# SCH_Business-Card_2024-07-06.net
KiCad netlist of a schematic drawn in EasyEDA
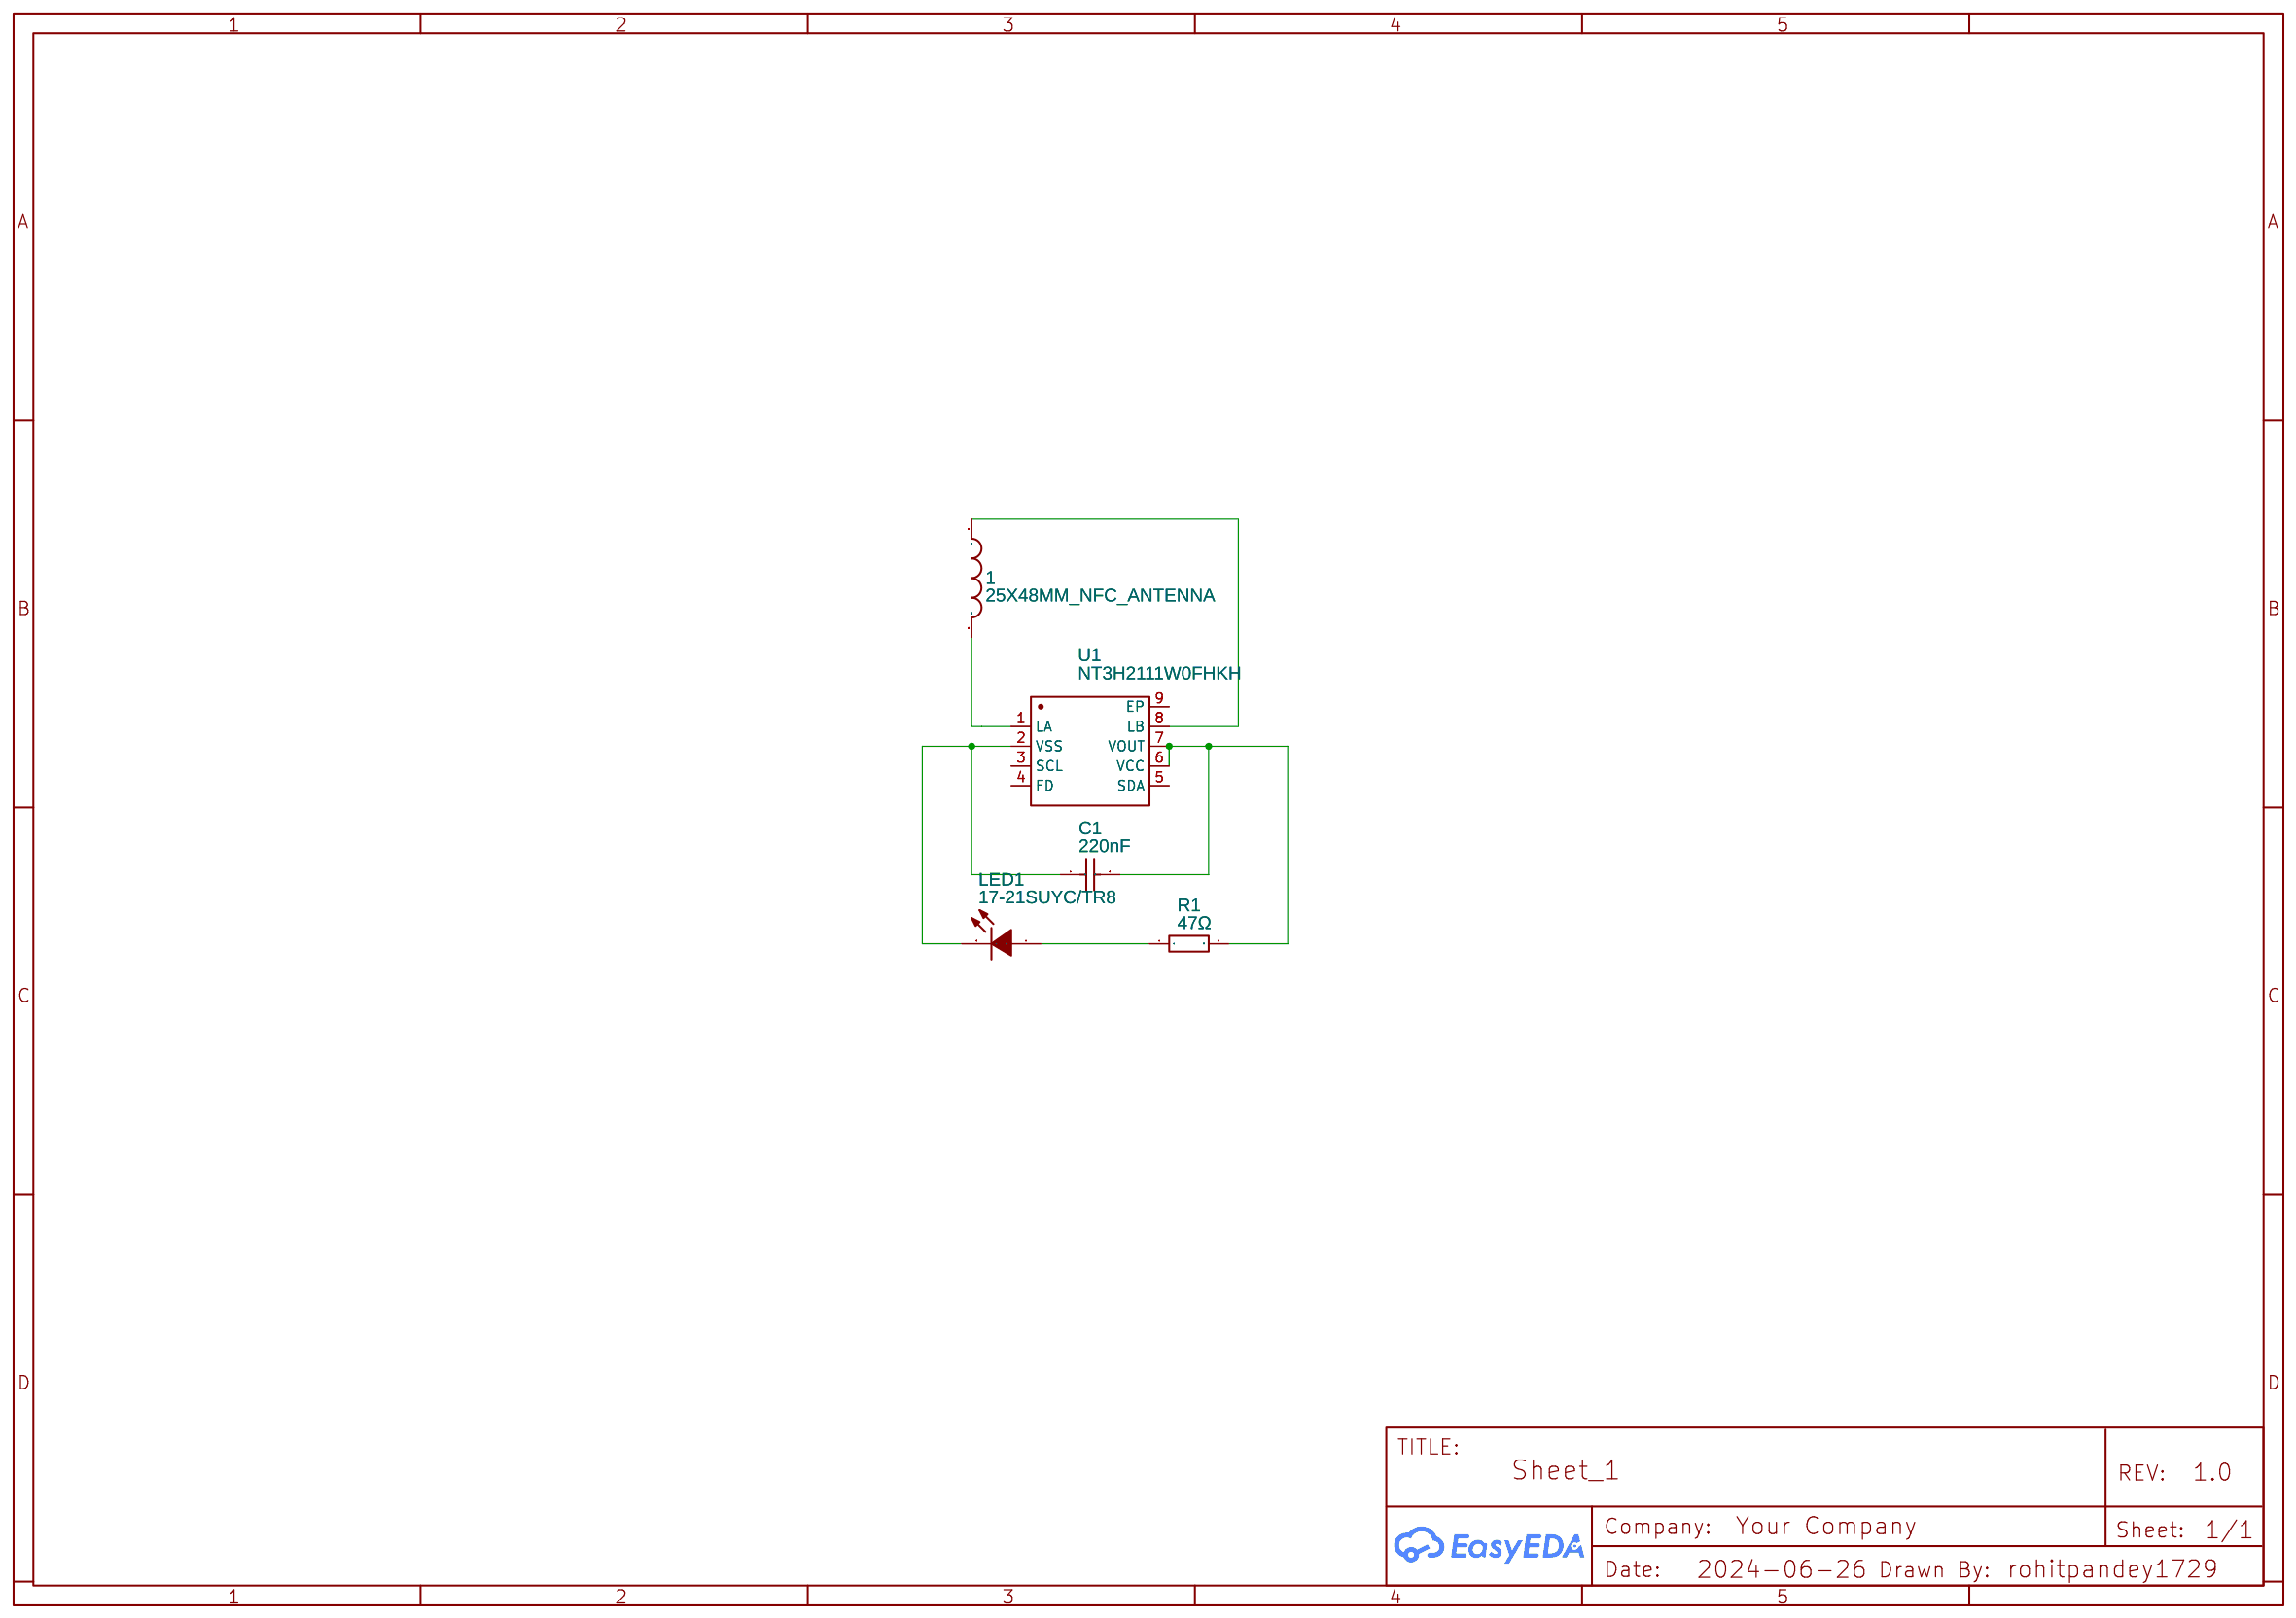
[diagram p0: schematic sheet]

(export (version "E")
  (design (tool "Eeschema 10.0.6"))
  (components
    (comp (ref "1") (value "25X48MM_NFC_ANTENNA") (libsource (lib "") (part "25X48MM_NFC_ANTENNA")))
    (comp (ref "C1")
      (value "220nF")
      (fields
        (field (name "Manufacturer Part") "CL10B224KA8NNNC")
        (field (name "Manufacturer") "SAMSUNG(三星)")
      )
      (libsource (lib "") (part "CL10B224KA8NNNC"))
    )
    (comp (ref "LED1")
      (value "17-21SUYC/TR8")
      (fields (field (name "Manufacturer Part") "KT-0805黄灯") (field (name "Manufacturer") "KENTO"))
      (libsource (lib "") (part "17-21SUYC/TR8"))
    )
    (comp (ref "R1")
      (value "47Ω")
      (fields
        (field (name "Manufacturer Part") "0603WAF470JT5E")
        (field (name "Manufacturer") "UNI-ROYAL(厚声)")
      )
      (libsource (lib "") (part "0603WAF470JT5E"))
    )
    (comp (ref "U1")
      (value "NT3H2111W0FHKH")
      (fields (field (name "Manufacturer") "NXP(恩智浦)"))
      (libsource (lib "") (part "NT3H2111W0FHKH"))
    )
  )
  (nets
    (net (code "1") (name "Net-(LED1-+)") (class "Default")
      (node (ref "LED1") (pin "1") (pinfunction "+_1") (pintype "unspecified"))
      (node (ref "R1") (pin "1") (pinfunction "1_1") (pintype "input"))
    )
    (net (code "2") (name "Net-(LED1--)") (class "Default")
      (node (ref "C1") (pin "1") (pinfunction "1_1") (pintype "input"))
      (node (ref "LED1") (pin "2") (pinfunction "-_2") (pintype "unspecified"))
      (node (ref "U1") (pin "2") (pinfunction "VSS_2") (pintype "unspecified"))
    )
    (net (code "3") (name "Net-(U1-LA)") (class "Default")
      (node (ref "1") (pin "P$2") (pinfunction "P$2_P$2") (pintype "bidirectional"))
      (node (ref "U1") (pin "1") (pinfunction "LA_1") (pintype "unspecified"))
    )
    (net (code "4") (name "Net-(U1-LB)") (class "Default")
      (node (ref "1") (pin "P$1") (pinfunction "P$1_P$1") (pintype "bidirectional"))
      (node (ref "U1") (pin "8") (pinfunction "LB_8") (pintype "unspecified"))
    )
    (net (code "5") (name "Net-(U1-VCC)") (class "Default")
      (node (ref "C1") (pin "2") (pinfunction "2_2") (pintype "input"))
      (node (ref "R1") (pin "2") (pinfunction "2_2") (pintype "input"))
      (node (ref "U1") (pin "6") (pinfunction "VCC_6") (pintype "unspecified"))
      (node (ref "U1") (pin "7") (pinfunction "VOUT_7") (pintype "unspecified"))
    )
    (net (code "6") (name "unconnected-(U1-EP-Pad9)") (class "Default")
      (node (ref "U1") (pin "9") (pinfunction "EP_9") (pintype "unspecified"))
    )
    (net (code "7") (name "unconnected-(U1-FD-Pad4)") (class "Default")
      (node (ref "U1") (pin "4") (pinfunction "FD_4") (pintype "unspecified"))
    )
    (net (code "8") (name "unconnected-(U1-SCL-Pad3)") (class "Default")
      (node (ref "U1") (pin "3") (pinfunction "SCL_3") (pintype "unspecified"))
    )
    (net (code "9") (name "unconnected-(U1-SDA-Pad5)") (class "Default")
      (node (ref "U1") (pin "5") (pinfunction "SDA_5") (pintype "unspecified"))
    )
  )
)
